# Voltage_reference.net
KiCad netlist of a schematic drawn in Altium Designer
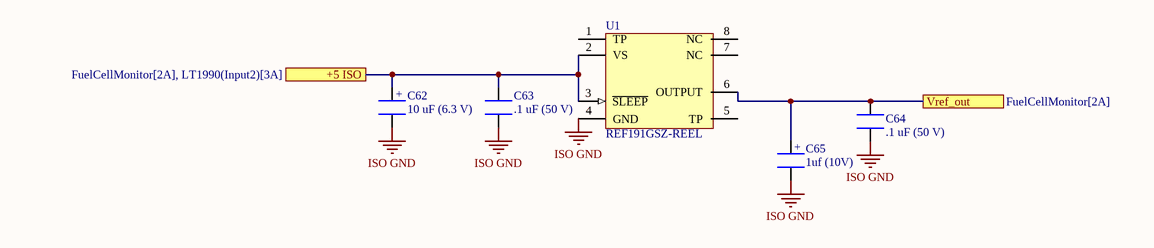
[diagram p0: Voltage reference.SchDoc]

(export (version "E")
  (design (tool "Eeschema 10.0.6"))
  (components
    (comp (ref "C62")
      (value "10 uF (6.3 V)")
      (footprint "10 uF cap")
      (libsource (lib "FuelCellMonitor") (part "10 uF cap"))
    )
    (comp (ref "C63")
      (value ".1 uF (50 V)")
      (footprint ".1uF capacitor")
      (libsource (lib "FuelCellMonitor") (part ".1 uF cap"))
    )
    (comp (ref "C64")
      (value ".1 uF (50 V)")
      (footprint ".1uF capacitor")
      (libsource (lib "FuelCellMonitor") (part ".1 uF cap"))
    )
    (comp (ref "C65")
      (value "1uf (10V)")
      (footprint "1 uF cap")
      (libsource (lib "FuelCellMonitor") (part "1uf cap"))
    )
    (comp (ref "U1")
      (value "REF191GSZ-REEL")
      (footprint "ADI-R-8_N")
      (fields (field (name "MANUFACTURER") "Analog Devices"))
      (libsource (lib "FuelCellMonitor") (part "REF191GSZ-REEL"))
    )
  )
  (nets
    (net (code "1") (name "/+5 ISO") (class "Default")
      (node (ref "C62") (pin "1") (pinfunction "1_1") (pintype "power_in"))
      (node (ref "C63") (pin "1") (pinfunction "1_1") (pintype "power_in"))
      (node (ref "U1") (pin "2") (pinfunction "VS_2") (pintype "power_in"))
      (node (ref "U1") (pin "3") (pinfunction "~{SLEEP}_3") (pintype "input"))
    )
    (net (code "2") (name "/Vref_out") (class "Default")
      (node (ref "C64") (pin "2") (pinfunction "2_2") (pintype "power_in"))
      (node (ref "C65") (pin "1") (pinfunction "1_1") (pintype "power_in"))
      (node (ref "U1") (pin "6") (pinfunction "OUTPUT_6") (pintype "tri_state"))
    )
    (net (code "3") (name "ISO GND") (class "Default")
      (node (ref "C62") (pin "2") (pinfunction "2_2") (pintype "power_in"))
      (node (ref "C63") (pin "2") (pinfunction "2_2") (pintype "power_in"))
      (node (ref "C64") (pin "1") (pinfunction "1_1") (pintype "power_in"))
      (node (ref "C65") (pin "2") (pinfunction "2_2") (pintype "power_in"))
      (node (ref "U1") (pin "4") (pinfunction "GND_4") (pintype "power_in"))
    )
    (net (code "4") (name "unconnected-(U1-NC-Pad7)") (class "Default")
      (node (ref "U1") (pin "7") (pinfunction "NC_7") (pintype "passive"))
    )
    (net (code "5") (name "unconnected-(U1-NC-Pad8)") (class "Default")
      (node (ref "U1") (pin "8") (pinfunction "NC_8") (pintype "passive"))
    )
    (net (code "6") (name "unconnected-(U1-TP-Pad1)") (class "Default")
      (node (ref "U1") (pin "1") (pinfunction "TP_1") (pintype "passive"))
    )
    (net (code "7") (name "unconnected-(U1-TP-Pad5)") (class "Default")
      (node (ref "U1") (pin "5") (pinfunction "TP_5") (pintype "passive"))
    )
  )
)
